# Keypadmacro.net
KiCad netlist of a schematic drawn in Altium Designer
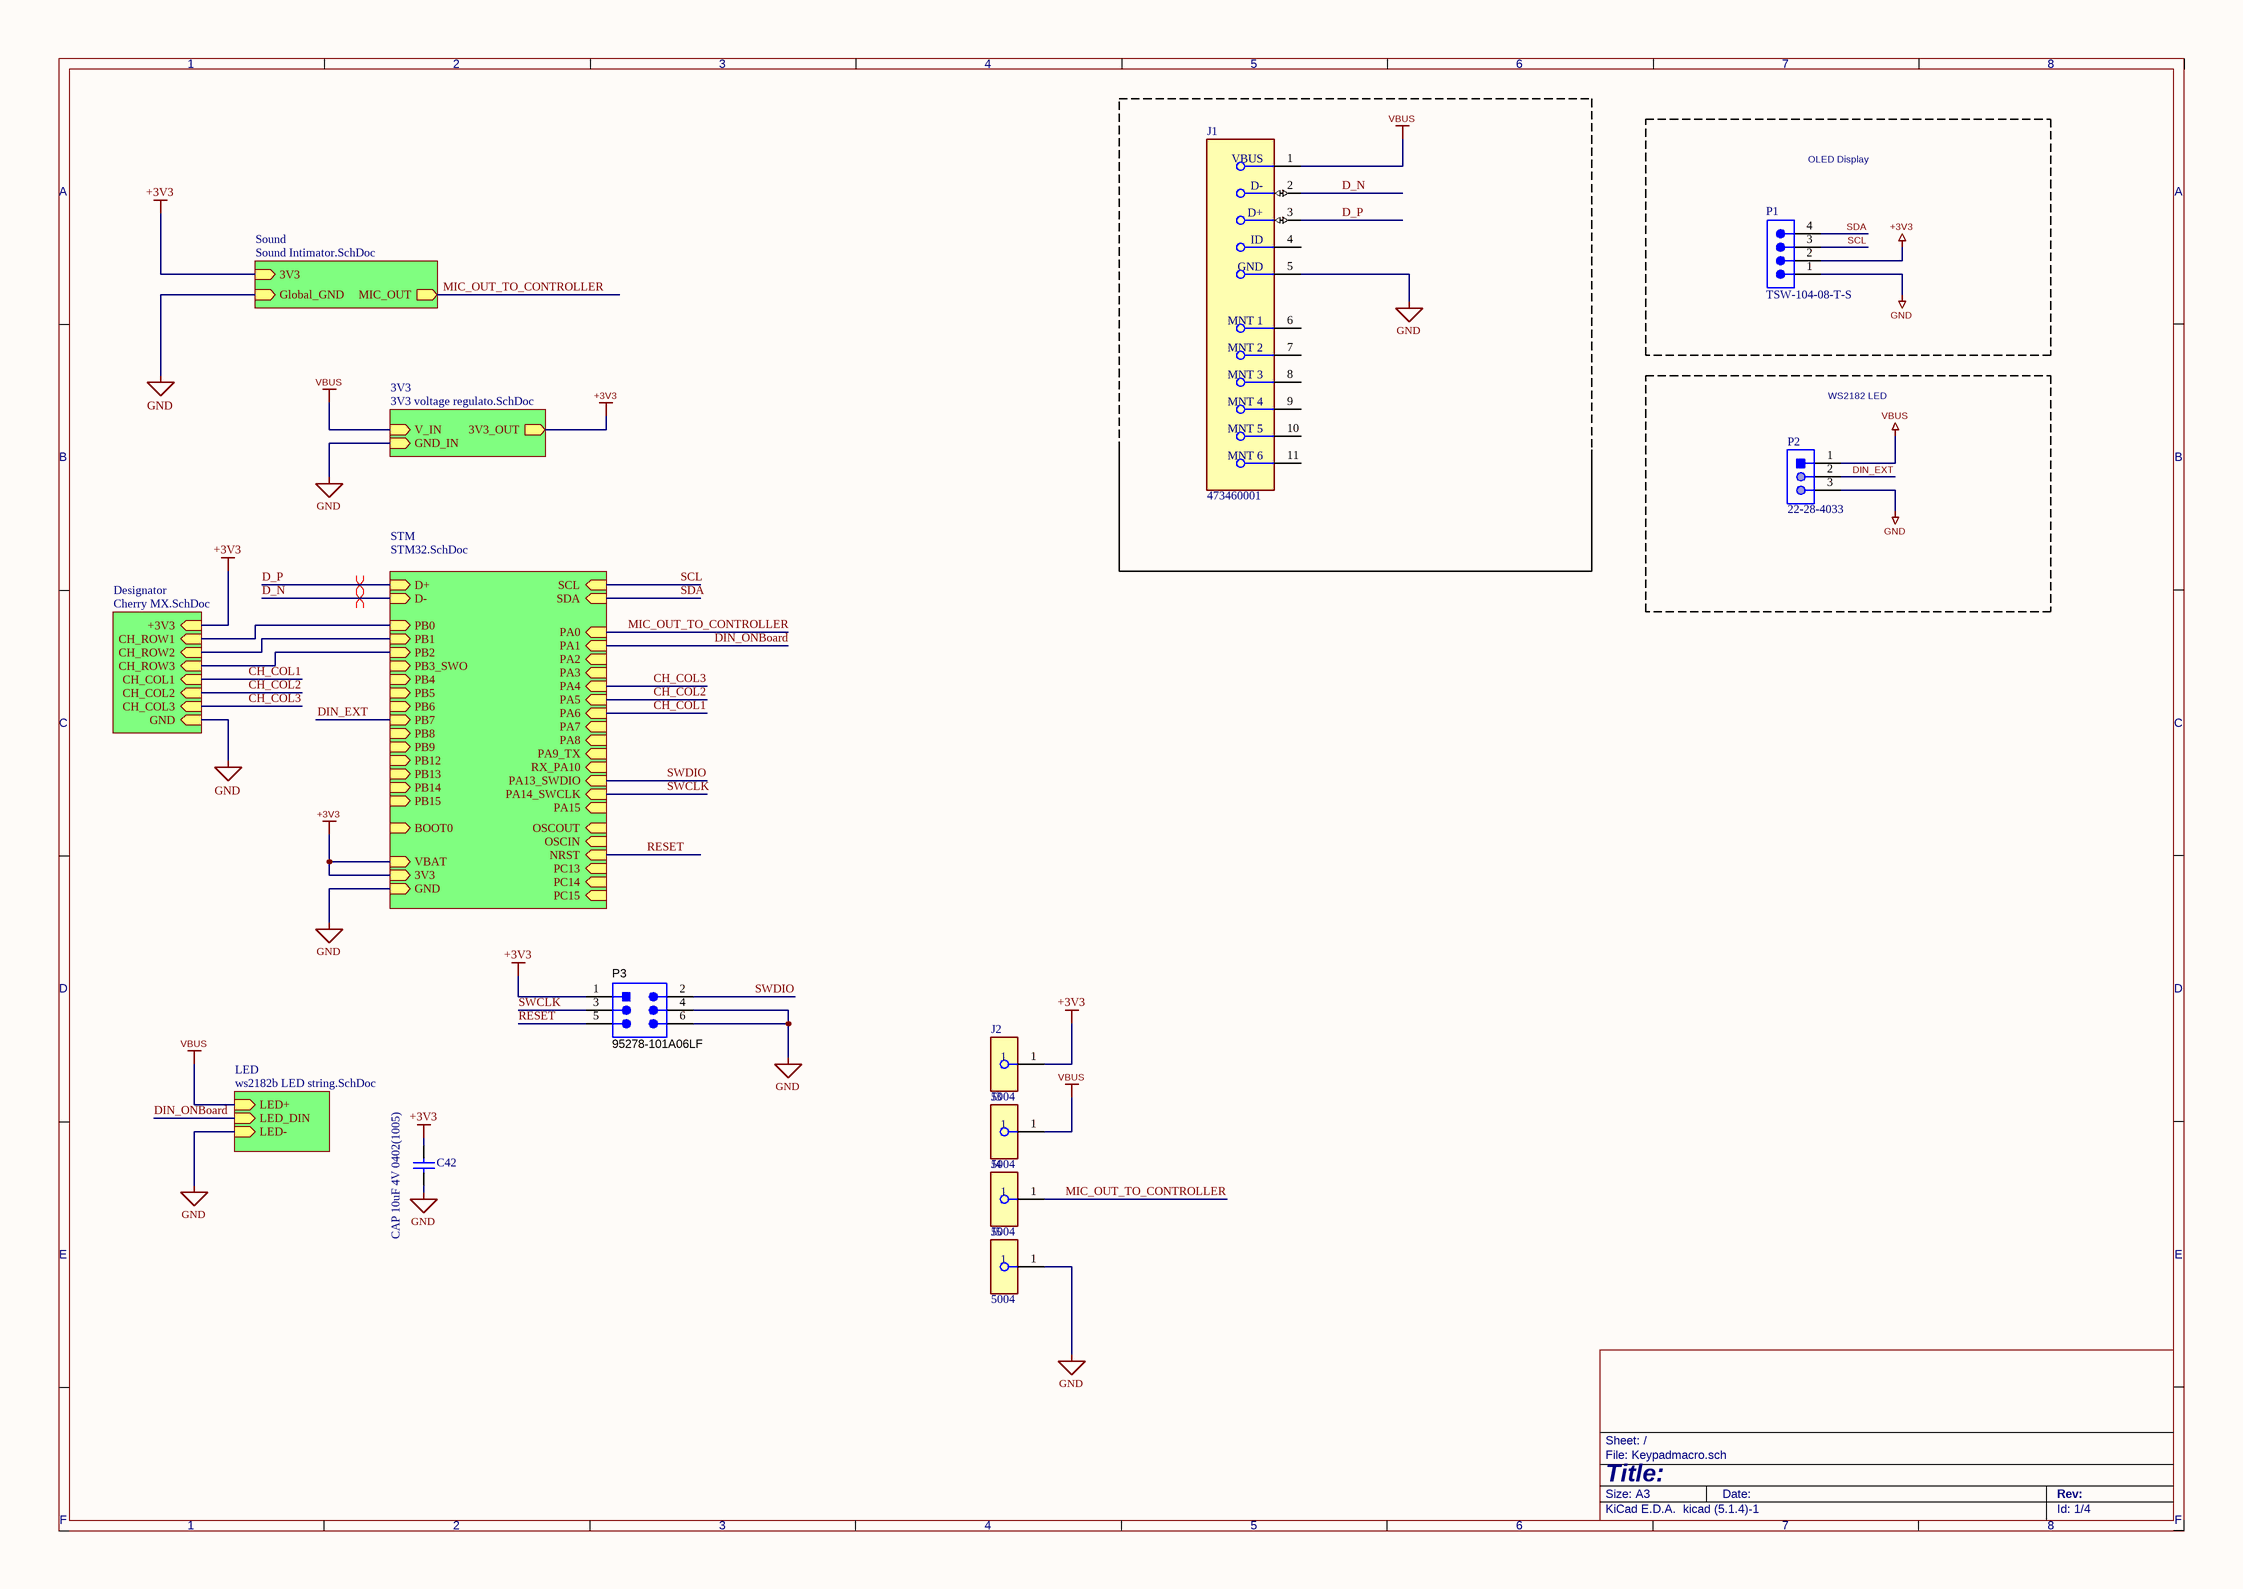
[diagram p0: Keypadmacro.SchDoc]

(export (version "E")
  (design (tool "Eeschema 10.0.6"))
  (components
    (comp (ref "C42")
      (value "CAP 10uF 4V 0402(1005)")
      (footprint "CAPC0402(1005)60_L")
      (description "CAP 10uF 4V ±20% 0402 (1005 Metric) Thickness 0.6mm SMD")
      (fields (field (name "TOLERANCE") "Â±20%"))
      (libsource (lib "Altium Content Vault") (part "CAP"))
    )
    (comp (ref "J1")
      (value "473460001")
      (footprint "FP-473460001-MFG")
      (description "CONN RCPT USB2.0 MICRO B SMD R/A")
      (fields
        (field (name "OCTOPART") "https://octopart.com/47346-0001-molex-7164928")
        (field (name "MANUFACTURER") "Molex")
      )
      (libsource (lib "Altium Content Vault") (part "53ae1f1d9b557310b43ca686e5bb76a"))
    )
    (comp (ref "J2")
      (value "5004")
      (footprint "FP-5004-MFG")
      (description "PC TEST POINT MINIATURE YELLOW")
      (fields
        (field (name "MANUFACTURER") "Keystone")
        (field (name "OCTOPART") "https://octopart.com/5004-keystone-28591")
      )
      (libsource (lib "Altium Content Vault") (part "98815daf2f2c152b0c43f5ab9800df6"))
    )
    (comp (ref "J3")
      (value "5004")
      (footprint "FP-5004-MFG")
      (description "PC TEST POINT MINIATURE YELLOW")
      (fields
        (field (name "MANUFACTURER") "Keystone")
        (field (name "OCTOPART") "https://octopart.com/5004-keystone-28591")
      )
      (libsource (lib "Altium Content Vault") (part "98815daf2f2c152b0c43f5ab9800df6"))
    )
    (comp (ref "J4")
      (value "5004")
      (footprint "FP-5004-MFG")
      (description "PC TEST POINT MINIATURE YELLOW")
      (fields
        (field (name "MANUFACTURER") "Keystone")
        (field (name "OCTOPART") "https://octopart.com/5004-keystone-28591")
      )
      (libsource (lib "Altium Content Vault") (part "98815daf2f2c152b0c43f5ab9800df6"))
    )
    (comp (ref "J5")
      (value "5004")
      (footprint "FP-5004-MFG")
      (description "PC TEST POINT MINIATURE YELLOW")
      (fields
        (field (name "MANUFACTURER") "Keystone")
        (field (name "OCTOPART") "https://octopart.com/5004-keystone-28591")
      )
      (libsource (lib "Altium Content Vault") (part "98815daf2f2c152b0c43f5ab9800df6"))
    )
    (comp (ref "P1")
      (value "TSW-104-08-T-S")
      (footprint "SMTC-TSW-104-08-X-S")
      (description "0.025\" SQ Post Header, Through-hole, Vertical, -55 to 105 degC, 2.54 mm Pitch, 4-Pin, Male, RoHS")
      (fields (field (name "MANUFACTURER") "Samtec"))
      (libsource (lib "Altium Content Vault") (part "SMTC-TSW-104-08-X-S"))
    )
    (comp (ref "P2")
      (value "22-28-4033")
      (footprint "MOLX-22-28-4033_V")
      (description "Male Header, Pitch 2.54 mm, 1 x 3 Position, Height 8.38 mm, Tail Length 3.18 mm, RoHS, Bulk")
      (fields (field (name "MANUFACTURER") "Molex"))
      (libsource (lib "Altium Content Vault") (part "CN-1P-M-R3"))
    )
    (comp (ref "P3")
      (value "95278-101A06LF")
      (footprint "AMPM-95278-101A06LF_V")
      (description "Male Header, Pitch 2.54 mm, 2 x 3 Position, Height 14.4 mm, RoHS, Tape and Reel")
      (fields (field (name "TOLERANCE") "1%"))
      (libsource (lib "Altium Content Vault") (part "CN-2P-M-R6"))
    )
  )
  (nets
    (net (code "1") (name "+3V3") (class "Default")
      (node (ref "C42") (pin "2") (pinfunction "2_2") (pintype "passive"))
      (node (ref "J2") (pin "1") (pinfunction "1_1") (pintype "passive"))
      (node (ref "P1") (pin "2") (pinfunction "2_2") (pintype "passive"))
      (node (ref "P3") (pin "1") (pinfunction "1_1") (pintype "passive"))
    )
    (net (code "9") (name "/DIN_EXT") (class "Default")
      (node (ref "P2") (pin "2") (pinfunction "2_2") (pintype "passive"))
    )
    (net (code "11") (name "/D_N") (class "Default")
      (node (ref "J1") (pin "2") (pinfunction "D-_2") (pintype "bidirectional"))
    )
    (net (code "12") (name "/D_P") (class "Default")
      (node (ref "J1") (pin "3") (pinfunction "D+_3") (pintype "bidirectional"))
    )
    (net (code "13") (name "/MIC_OUT_TO_CONTROLLER") (class "Default")
      (node (ref "J4") (pin "1") (pinfunction "1_1") (pintype "passive"))
    )
    (net (code "35") (name "/RESET") (class "Default")
      (node (ref "P3") (pin "5") (pinfunction "5_5") (pintype "passive"))
    )
    (net (code "37") (name "/SCL") (class "Default")
      (node (ref "P1") (pin "3") (pinfunction "3_3") (pintype "passive"))
    )
    (net (code "38") (name "/SDA") (class "Default")
      (node (ref "P1") (pin "4") (pinfunction "4_4") (pintype "passive"))
    )
    (net (code "39") (name "/SWCLK") (class "Default")
      (node (ref "P3") (pin "3") (pinfunction "3_3") (pintype "passive"))
    )
    (net (code "40") (name "/SWDIO") (class "Default")
      (node (ref "P3") (pin "2") (pinfunction "2_2") (pintype "passive"))
    )
    (net (code "41") (name "GND") (class "Default")
      (node (ref "C42") (pin "1") (pinfunction "1_1") (pintype "passive"))
      (node (ref "J1") (pin "5") (pinfunction "GND_5") (pintype "power_in"))
      (node (ref "J5") (pin "1") (pinfunction "1_1") (pintype "passive"))
      (node (ref "P1") (pin "1") (pinfunction "1_1") (pintype "passive"))
      (node (ref "P2") (pin "3") (pinfunction "3_3") (pintype "passive"))
      (node (ref "P3") (pin "4") (pinfunction "4_4") (pintype "passive"))
      (node (ref "P3") (pin "6") (pinfunction "6_6") (pintype "passive"))
    )
    (net (code "42") (name "VBUS") (class "Default")
      (node (ref "J1") (pin "1") (pinfunction "VBUS_1") (pintype "power_in"))
      (node (ref "J3") (pin "1") (pinfunction "1_1") (pintype "passive"))
      (node (ref "P2") (pin "1") (pinfunction "1_1") (pintype "passive"))
    )
    (net (code "43") (name "unconnected-(J1-ID-Pad4)") (class "Default")
      (node (ref "J1") (pin "4") (pinfunction "ID_4") (pintype "passive"))
    )
    (net (code "44") (name "unconnected-(J1-MNT_1-Pad6)") (class "Default")
      (node (ref "J1") (pin "6") (pinfunction "MNT_1_6") (pintype "passive"))
    )
    (net (code "45") (name "unconnected-(J1-MNT_2-Pad7)") (class "Default")
      (node (ref "J1") (pin "7") (pinfunction "MNT_2_7") (pintype "passive"))
    )
    (net (code "46") (name "unconnected-(J1-MNT_3-Pad8)") (class "Default")
      (node (ref "J1") (pin "8") (pinfunction "MNT_3_8") (pintype "passive"))
    )
    (net (code "47") (name "unconnected-(J1-MNT_4-Pad9)") (class "Default")
      (node (ref "J1") (pin "9") (pinfunction "MNT_4_9") (pintype "passive"))
    )
    (net (code "48") (name "unconnected-(J1-MNT_5-Pad10)") (class "Default")
      (node (ref "J1") (pin "10") (pinfunction "MNT_5_10") (pintype "passive"))
    )
    (net (code "49") (name "unconnected-(J1-MNT_6-Pad11)") (class "Default")
      (node (ref "J1") (pin "11") (pinfunction "MNT_6_11") (pintype "passive"))
    )
  )
)
